# T_l_commande.net
KiCad netlist of a schematic drawn in Altium Designer
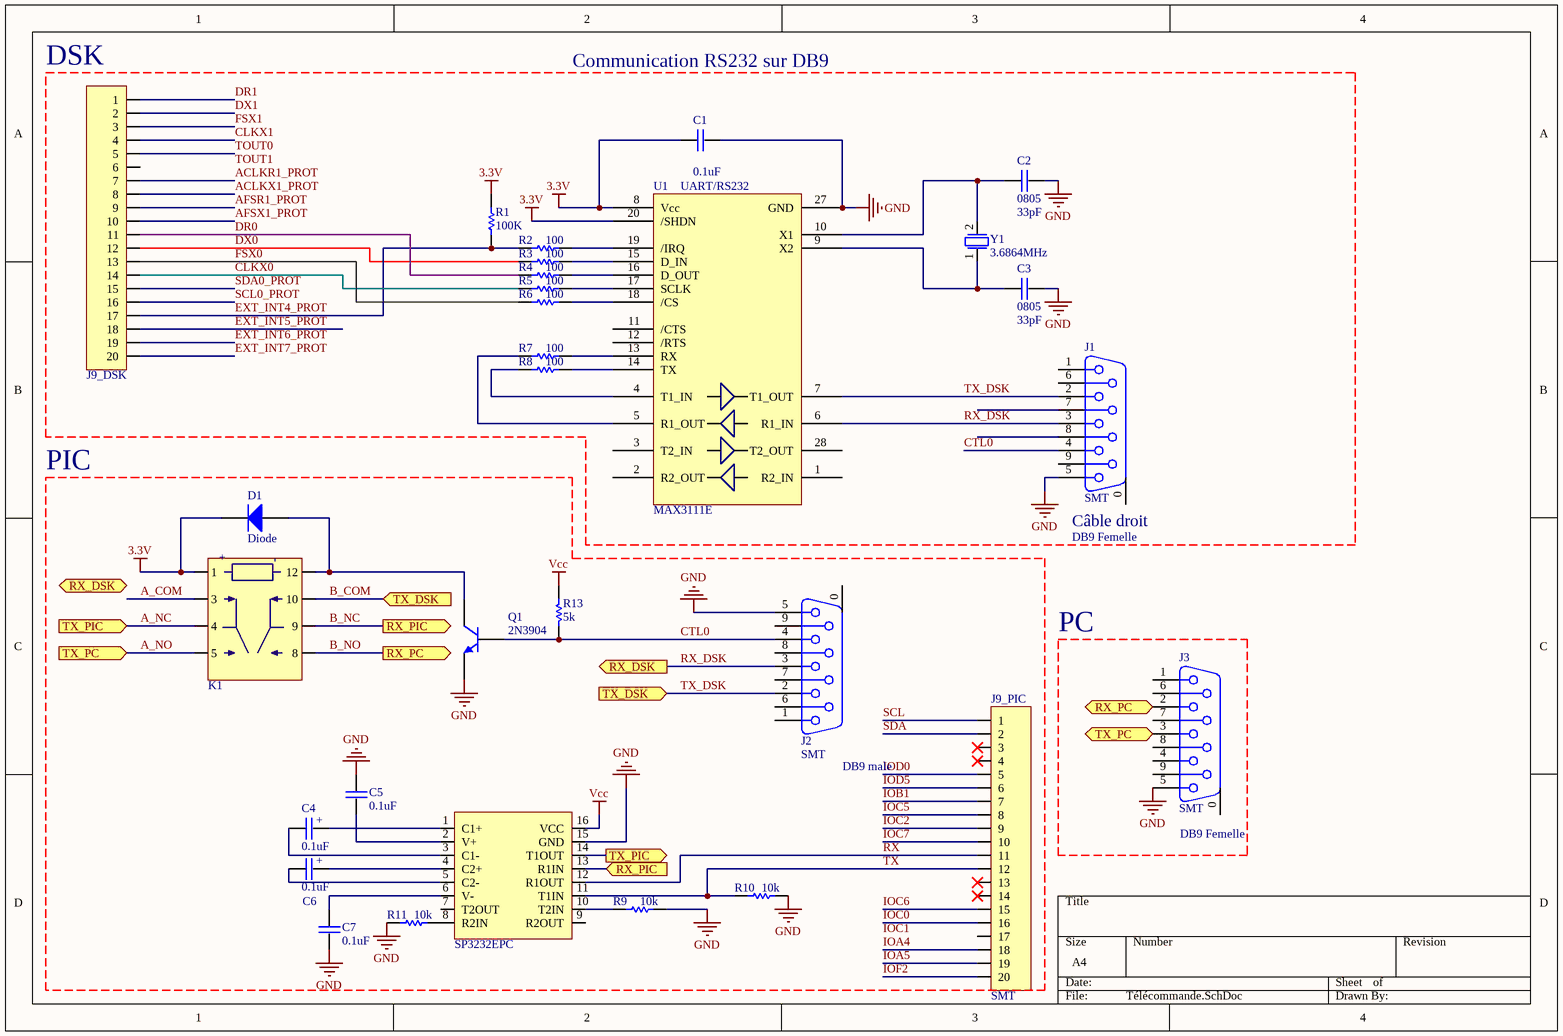
[diagram p0: Télécommande.SchDoc]

(export (version "E")
  (design (tool "Eeschema 10.0.6"))
  (components
    (comp (ref "C1")
      (value "0.1uF")
      (footprint "0805")
      (description "Condensateur céramique 0.1uF")
      (fields
        (field (name "MANUFACTURER") "Samsung Electro-Mechanics America, Inc.")
        (field (name "MFG PART NUMBER") "CL21B104KBCNNNC")
        (field (name "CREATEDBY") "Mathieu G-M")
        (field (name "VERIFIEDBY") "*")
      )
      (libsource (lib "SchLib_PCBs5") (part "Cap 0.1uF"))
    )
    (comp (ref "C2")
      (value "33pF")
      (footprint "0805")
      (description "Condensateur céramique 39pF")
      (fields
        (field (name "MANUFACTURER") "Samsung Electro-Mechanics America, Inc.")
        (field (name "MFG PART NUMBER") "CL21C390JBANNNC")
        (field (name "PACKAGE") "0805")
        (field (name "CREATEDBY") "Chloe Mireault-Lecourt")
        (field (name "VERIFIEDBY") "Olivier Bernard")
      )
      (libsource (lib "SchLib_PCBs5") (part "Cap 39pF"))
    )
    (comp (ref "C3")
      (value "33pF")
      (footprint "0805")
      (description "Condensateur céramique 39pF")
      (fields
        (field (name "MANUFACTURER") "Samsung Electro-Mechanics America, Inc.")
        (field (name "MFG PART NUMBER") "CL21C390JBANNNC")
        (field (name "PACKAGE") "0805")
        (field (name "CREATEDBY") "Chloe Mireault-Lecourt")
        (field (name "VERIFIEDBY") "Olivier Bernard")
      )
      (libsource (lib "SchLib_PCBs5") (part "Cap 39pF"))
    )
    (comp (ref "C4")
      (value "0.1uF")
      (footprint "0805")
      (description "Condensateur céramique 0.1uF")
      (fields
        (field (name "MANUFACTURER") "Samsung Electro-Mechanics America, Inc.")
        (field (name "MFG PART NUMBER") "CL21B104KBCNNNC")
        (field (name "CREATEDBY") "Mathieu G-M")
        (field (name "VERIFIEDBY") "*")
      )
      (libsource (lib "SchLib_PCBs5") (part "Cap 0.1uF"))
    )
    (comp (ref "C5")
      (value "0.1uF")
      (footprint "0805")
      (description "Condensateur céramique 0.1uF")
      (fields
        (field (name "MANUFACTURER") "Samsung Electro-Mechanics America, Inc.")
        (field (name "MFG PART NUMBER") "CL21B104KBCNNNC")
        (field (name "CREATEDBY") "Mathieu G-M")
        (field (name "VERIFIEDBY") "*")
      )
      (libsource (lib "SchLib_PCBs5") (part "Cap 0.1uF"))
    )
    (comp (ref "C6")
      (value "0.1uF")
      (footprint "0805")
      (description "Condensateur céramique 0.1uF")
      (fields
        (field (name "MANUFACTURER") "Samsung Electro-Mechanics America, Inc.")
        (field (name "MFG PART NUMBER") "CL21B104KBCNNNC")
        (field (name "CREATEDBY") "Mathieu G-M")
        (field (name "VERIFIEDBY") "*")
      )
      (libsource (lib "SchLib_PCBs5") (part "Cap 0.1uF"))
    )
    (comp (ref "C7")
      (value "0.1uF")
      (footprint "0805")
      (description "Condensateur céramique 0.1uF")
      (fields
        (field (name "MANUFACTURER") "Samsung Electro-Mechanics America, Inc.")
        (field (name "MFG PART NUMBER") "CL21B104KBCNNNC")
        (field (name "CREATEDBY") "Mathieu G-M")
        (field (name "VERIFIEDBY") "*")
      )
      (libsource (lib "SchLib_PCBs5") (part "Cap 0.1uF"))
    )
    (comp (ref "D1")
      (value "Diode")
      (footprint "SMC")
      (description "Default Diode")
      (fields (field (name "PUBLISHER") "Altium Limited"))
      (libsource (lib "Miscellaneous Devices") (part "Diode"))
    )
    (comp (ref "J1")
      (value "Conn DB9")
      (footprint "DB9 connector - SMT")
      (description "DB9 connecteur femelle")
      (fields
        (field (name "VOLTAGE") "300V")
        (field (name "MANUFACTURER") "Amphenol Commercial Products")
        (field (name "PACKAGE") "SMT")
        (field (name "CREATEDBY") "Mathieu G-M")
        (field (name "VERIFIEDBY") "*")
      )
      (libsource (lib "SchLib_PCBs5") (part "Conn DB9"))
    )
    (comp (ref "J2")
      (value "Conn DB9")
      (footprint "DB9 connector - SMT")
      (description "DB9 connecteur femelle")
      (fields
        (field (name "VOLTAGE") "300V")
        (field (name "MANUFACTURER") "Amphenol Commercial Products")
        (field (name "PACKAGE") "SMT")
        (field (name "CREATEDBY") "Mathieu G-M")
        (field (name "VERIFIEDBY") "*")
      )
      (libsource (lib "") (part "Conn DB9_1"))
    )
    (comp (ref "J3")
      (value "Conn DB9")
      (footprint "DB9 connector - SMT")
      (description "DB9 connecteur femelle")
      (fields
        (field (name "VOLTAGE") "300V")
        (field (name "MANUFACTURER") "Amphenol Commercial Products")
        (field (name "PACKAGE") "SMT")
        (field (name "CREATEDBY") "Mathieu G-M")
        (field (name "VERIFIEDBY") "*")
      )
      (libsource (lib "SchLib_PCBs5") (part "Conn DB9"))
    )
    (comp (ref "J9_DSK")
      (value "Conn20pinsF")
      (footprint "Conn_20_SMT")
      (description "Connecteur 20 pins F - pitch = 100mils")
      (fields
        (field (name "MANUFACTURER") "Sullins Connector Solutions")
        (field (name "MFG PART NUMBER") "NPTC102KFMS-RC")
        (field (name "CREATEDBY") "Olivier Bernard")
        (field (name "VERIFIEDBY") "*")
      )
      (libsource (lib "") (part "Conn20pinsF_1"))
    )
    (comp (ref "J9_PIC")
      (value "Conn20pinsF")
      (footprint "Conn_20_SMT")
      (description "Connecteur 20 pins F - pitch = 100mils")
      (fields
        (field (name "MANUFACTURER") "Sullins Connector Solutions")
        (field (name "MFG PART NUMBER") "NPTC102KFMS-RC")
        (field (name "PACKAGE") "SMT")
        (field (name "CREATEDBY") "Olivier Bernard")
        (field (name "VERIFIEDBY") "*")
      )
      (libsource (lib "SchLib_PCBs5") (part "Conn20pinsF"))
    )
    (comp (ref "K1")
      (value "Relay 3V")
      (footprint "Relay_3V")
      (fields
        (field (name "VOLTAGE") "Turn ON (2.4V), Turn OFF (0.3V)")
        (field (name "POWER") "coil Power (50mW)")
        (field (name "MANUFACTURER") "Panasonic Electric Works")
        (field (name "CREATEDBY") "Chloe Mireault-Lecourt")
        (field (name "VERIFIEDBY") "Olivier Bernard")
      )
      (libsource (lib "SchLib_PCBs5") (part "Relay 3V"))
    )
    (comp (ref "Q1")
      (value "2N3904")
      (footprint "TO-92A")
      (description "NPN General Purpose Amplifier")
      (fields (field (name "PUBLISHER") "Altium Limited"))
      (libsource (lib "Miscellaneous Devices") (part "2N3904"))
    )
    (comp (ref "R1")
      (value "100K")
      (footprint "0805")
      (description "Res 100k - SMT - 0805")
      (fields
        (field (name "POWER") "1/8W")
        (field (name "MANUFACTURER") "Yageo")
        (field (name "CREATEDBY") "Olivier Bernard")
        (field (name "VERIFIEDBY") "*")
      )
      (libsource (lib "SchLib_PCBs5") (part "Res100k_1%"))
    )
    (comp (ref "R2")
      (value "100")
      (footprint "0805")
      (description "Res 100- SMT - 0805")
      (fields
        (field (name "POWER") "1/8W")
        (field (name "MANUFACTURER") "Yageo")
        (field (name "CREATEDBY") "Olivier Bernard")
        (field (name "VERIFIEDBY") "*")
      )
      (libsource (lib "SchLib_PCBs5") (part "Res100_1%"))
    )
    (comp (ref "R3")
      (value "100")
      (footprint "0805")
      (description "Res 100- SMT - 0805")
      (fields
        (field (name "POWER") "1/8W")
        (field (name "MANUFACTURER") "Yageo")
        (field (name "CREATEDBY") "Olivier Bernard")
        (field (name "VERIFIEDBY") "*")
      )
      (libsource (lib "SchLib_PCBs5") (part "Res100_1%"))
    )
    (comp (ref "R4")
      (value "100")
      (footprint "0805")
      (description "Res 100- SMT - 0805")
      (fields
        (field (name "POWER") "1/8W")
        (field (name "MANUFACTURER") "Yageo")
        (field (name "CREATEDBY") "Olivier Bernard")
        (field (name "VERIFIEDBY") "*")
      )
      (libsource (lib "SchLib_PCBs5") (part "Res100_1%"))
    )
    (comp (ref "R5")
      (value "100")
      (footprint "0805")
      (description "Res 100- SMT - 0805")
      (fields
        (field (name "POWER") "1/8W")
        (field (name "MANUFACTURER") "Yageo")
        (field (name "CREATEDBY") "Olivier Bernard")
        (field (name "VERIFIEDBY") "*")
      )
      (libsource (lib "SchLib_PCBs5") (part "Res100_1%"))
    )
    (comp (ref "R6")
      (value "100")
      (footprint "0805")
      (description "Res 100- SMT - 0805")
      (fields
        (field (name "POWER") "1/8W")
        (field (name "MANUFACTURER") "Yageo")
        (field (name "CREATEDBY") "Olivier Bernard")
        (field (name "VERIFIEDBY") "*")
      )
      (libsource (lib "SchLib_PCBs5") (part "Res100_1%"))
    )
    (comp (ref "R7")
      (value "100")
      (footprint "0805")
      (description "Res 100- SMT - 0805")
      (fields
        (field (name "POWER") "1/8W")
        (field (name "MANUFACTURER") "Yageo")
        (field (name "CREATEDBY") "Olivier Bernard")
        (field (name "VERIFIEDBY") "*")
      )
      (libsource (lib "SchLib_PCBs5") (part "Res100_1%"))
    )
    (comp (ref "R8")
      (value "100")
      (footprint "0805")
      (description "Res 100- SMT - 0805")
      (fields
        (field (name "POWER") "1/8W")
        (field (name "MANUFACTURER") "Yageo")
        (field (name "CREATEDBY") "Olivier Bernard")
        (field (name "VERIFIEDBY") "*")
      )
      (libsource (lib "SchLib_PCBs5") (part "Res100_1%"))
    )
    (comp (ref "R9")
      (value "10k")
      (footprint "0805")
      (description "Res 100- SMT - 0805")
      (fields
        (field (name "POWER") "1/8W")
        (field (name "MANUFACTURER") "Yageo")
        (field (name "CREATEDBY") "Olivier Bernard")
        (field (name "VERIFIEDBY") "*")
      )
      (libsource (lib "SchLib_PCBs5") (part "Res100_1%"))
    )
    (comp (ref "R10")
      (value "10k")
      (footprint "0805")
      (description "Res 100- SMT - 0805")
      (fields
        (field (name "POWER") "1/8W")
        (field (name "MANUFACTURER") "Yageo")
        (field (name "CREATEDBY") "Olivier Bernard")
        (field (name "VERIFIEDBY") "*")
      )
      (libsource (lib "SchLib_PCBs5") (part "Res100_1%"))
    )
    (comp (ref "R11")
      (value "10k")
      (footprint "0805")
      (description "Res 100- SMT - 0805")
      (fields
        (field (name "POWER") "1/8W")
        (field (name "MANUFACTURER") "Yageo")
        (field (name "CREATEDBY") "Olivier Bernard")
        (field (name "VERIFIEDBY") "*")
      )
      (libsource (lib "SchLib_PCBs5") (part "Res100_1%"))
    )
    (comp (ref "R13")
      (value "5k")
      (footprint "0805")
      (description "Res 100k - SMT - 0805")
      (fields
        (field (name "POWER") "1/8W")
        (field (name "MANUFACTURER") "Yageo")
        (field (name "CREATEDBY") "Olivier Bernard")
        (field (name "VERIFIEDBY") "*")
      )
      (libsource (lib "SchLib_PCBs5") (part "Res100k_1%"))
    )
    (comp (ref "SP3232EPC")
      (value "SP3232EPC")
      (footprint "board-2-board40p_M")
      (description "40 Position Connector Header, Outer Shroud Contacts Surface Mount, Right Angle Gold")
      (fields
        (field (name "MANUFACTURER") "Hirose Electric Co Ltd")
        (field (name "MFG PART NUMBER") "FX18-40P-0.8SH")
        (field (name "HELPURL") "file:///C:/Users/Olivier/Downloads/FX18_05790002500_2d.pdf")
        (field (name "CREATEDBY") "BJong")
        (field (name "VERIFIEDBY") "Olivier Bernard")
      )
      (libsource (lib "SchLib_PCBs5") (part "SP3232EPC"))
    )
    (comp (ref "U1")
      (value "MAX3111E")
      (footprint "SOIC-28")
      (description "SPI/MICROWIRE Compatible UART and RS-232 Transceiver")
      (fields
        (field (name "MANUFACTURER") "Maxim Integrated")
        (field (name "MFG PART NUMBER") "MAX3111ECWI+G36")
        (field (name "CREATEDBY") "Chloe Mireault-Lecourt")
        (field (name "VERIFIEDBY") "Olivier Bernard")
      )
      (libsource (lib "SchLib_PCBs5") (part "MAX3111E"))
    )
    (comp (ref "Y1")
      (value "3.6864MHz")
      (footprint "Cristal HC49/US")
      (description "Crystal 3.6864MHz - SMT - HC49/US")
      (fields
        (field (name "MANUFACTURER") "Fox Electronics")
        (field (name "MFG PART NUMBER") "FOXSDLF/0368-20")
        (field (name "CREATEDBY") "Chloe Mireault-Lecourt")
        (field (name "VERIFIEDBY") "Olivier Bernard")
      )
      (libsource (lib "SchLib_PCBs5") (part "Crystal_3.6864"))
    )
  )
  (nets
    (net (code "1") (name "/ACLKR1_PROT") (class "Default")
      (node (ref "J9_DSK") (pin "7") (pinfunction "7_7") (pintype "passive"))
    )
    (net (code "2") (name "/ACLKX1_PROT") (class "Default")
      (node (ref "J9_DSK") (pin "8") (pinfunction "8_8") (pintype "passive"))
    )
    (net (code "3") (name "/AFSR1_PROT") (class "Default")
      (node (ref "J9_DSK") (pin "9") (pinfunction "9_9") (pintype "passive"))
    )
    (net (code "4") (name "/AFSX1_PROT") (class "Default")
      (node (ref "J9_DSK") (pin "10") (pinfunction "10_10") (pintype "passive"))
    )
    (net (code "5") (name "/A_COM") (class "Default")
      (node (ref "K1") (pin "3") (pinfunction "3_3") (pintype "passive"))
    )
    (net (code "6") (name "/A_NC") (class "Default")
      (node (ref "K1") (pin "4") (pinfunction "4_4") (pintype "passive"))
      (node (ref "SP3232EPC") (pin "14") (pinfunction "T1OUT_14") (pintype "passive"))
    )
    (net (code "7") (name "/A_NO") (class "Default")
      (node (ref "J3") (pin "3") (pinfunction "3_3") (pintype "passive"))
      (node (ref "K1") (pin "5") (pinfunction "5_5") (pintype "passive"))
    )
    (net (code "8") (name "/B_COM") (class "Default")
      (node (ref "J1") (pin "2") (pinfunction "2_2") (pintype "passive"))
      (node (ref "J2") (pin "2") (pinfunction "2_2") (pintype "passive"))
      (node (ref "K1") (pin "10") (pinfunction "10_10") (pintype "passive"))
      (node (ref "U1") (pin "7") (pinfunction "T1_OUT_7") (pintype "passive"))
    )
    (net (code "9") (name "/B_NC") (class "Default")
      (node (ref "K1") (pin "9") (pinfunction "9_9") (pintype "passive"))
      (node (ref "SP3232EPC") (pin "13") (pinfunction "R1IN_13") (pintype "passive"))
    )
    (net (code "10") (name "/B_NO") (class "Default")
      (node (ref "J3") (pin "2") (pinfunction "2_2") (pintype "passive"))
      (node (ref "K1") (pin "8") (pinfunction "8_8") (pintype "passive"))
    )
    (net (code "11") (name "/CLKX0") (class "Default")
      (node (ref "J9_DSK") (pin "14") (pinfunction "14_14") (pintype "passive"))
      (node (ref "R5") (pin "1") (pinfunction "1_1") (pintype "passive"))
    )
    (net (code "12") (name "/CLKX1") (class "Default")
      (node (ref "J9_DSK") (pin "4") (pinfunction "4_4") (pintype "passive"))
    )
    (net (code "13") (name "/CTL0") (class "Default")
      (node (ref "J1") (pin "4") (pinfunction "4_4") (pintype "passive"))
      (node (ref "J2") (pin "4") (pinfunction "4_4") (pintype "passive"))
      (node (ref "Q1") (pin "2") (pinfunction "B_2") (pintype "passive"))
      (node (ref "R13") (pin "1") (pinfunction "1_1") (pintype "passive"))
    )
    (net (code "14") (name "/DR0") (class "Default")
      (node (ref "J9_DSK") (pin "11") (pinfunction "11_11") (pintype "passive"))
      (node (ref "R4") (pin "1") (pinfunction "1_1") (pintype "passive"))
    )
    (net (code "15") (name "/DR1") (class "Default")
      (node (ref "J9_DSK") (pin "1") (pinfunction "1_1") (pintype "passive"))
    )
    (net (code "16") (name "/DX0") (class "Default")
      (node (ref "J9_DSK") (pin "12") (pinfunction "12_12") (pintype "passive"))
      (node (ref "R3") (pin "1") (pinfunction "1_1") (pintype "passive"))
    )
    (net (code "17") (name "/DX1") (class "Default")
      (node (ref "J9_DSK") (pin "2") (pinfunction "2_2") (pintype "passive"))
    )
    (net (code "18") (name "/EXT_INT4_PROT") (class "Default")
      (node (ref "J9_DSK") (pin "17") (pinfunction "17_17") (pintype "passive"))
      (node (ref "R1") (pin "1") (pinfunction "1_1") (pintype "passive"))
      (node (ref "R2") (pin "1") (pinfunction "1_1") (pintype "passive"))
    )
    (net (code "19") (name "/EXT_INT5_PROT") (class "Default")
      (node (ref "J9_DSK") (pin "18") (pinfunction "18_18") (pintype "passive"))
    )
    (net (code "20") (name "/EXT_INT6_PROT") (class "Default")
      (node (ref "J9_DSK") (pin "19") (pinfunction "19_19") (pintype "passive"))
    )
    (net (code "21") (name "/EXT_INT7_PROT") (class "Default")
      (node (ref "J9_DSK") (pin "20") (pinfunction "20_20") (pintype "passive"))
    )
    (net (code "22") (name "/FSX0") (class "Default")
      (node (ref "J9_DSK") (pin "13") (pinfunction "13_13") (pintype "passive"))
      (node (ref "R6") (pin "1") (pinfunction "1_1") (pintype "passive"))
    )
    (net (code "23") (name "/FSX1") (class "Default")
      (node (ref "J9_DSK") (pin "3") (pinfunction "3_3") (pintype "passive"))
    )
    (net (code "24") (name "/IOA4") (class "Default")
      (node (ref "J9_PIC") (pin "18") (pinfunction "18_18") (pintype "passive"))
    )
    (net (code "25") (name "/IOA5") (class "Default")
      (node (ref "J9_PIC") (pin "19") (pinfunction "19_19") (pintype "passive"))
    )
    (net (code "26") (name "/IOB1") (class "Default")
      (node (ref "J9_PIC") (pin "7") (pinfunction "7_7") (pintype "passive"))
    )
    (net (code "27") (name "/IOC0") (class "Default")
      (node (ref "J9_PIC") (pin "16") (pinfunction "16_16") (pintype "passive"))
    )
    (net (code "29") (name "/IOC2") (class "Default")
      (node (ref "J9_PIC") (pin "9") (pinfunction "9_9") (pintype "passive"))
    )
    (net (code "30") (name "/IOC5") (class "Default")
      (node (ref "J9_PIC") (pin "8") (pinfunction "8_8") (pintype "passive"))
    )
    (net (code "31") (name "/IOC6") (class "Default")
      (node (ref "J9_PIC") (pin "15") (pinfunction "15_15") (pintype "passive"))
    )
    (net (code "32") (name "/IOC7") (class "Default")
      (node (ref "J9_PIC") (pin "10") (pinfunction "10_10") (pintype "passive"))
    )
    (net (code "33") (name "/IOD0") (class "Default")
      (node (ref "J9_PIC") (pin "5") (pinfunction "5_5") (pintype "passive"))
    )
    (net (code "34") (name "/IOD5") (class "Default")
      (node (ref "J9_PIC") (pin "6") (pinfunction "6_6") (pintype "passive"))
    )
    (net (code "35") (name "/IOF2") (class "Default")
      (node (ref "J9_PIC") (pin "20") (pinfunction "20_20") (pintype "passive"))
    )
    (net (code "36") (name "/RX") (class "Default")
      (node (ref "J9_PIC") (pin "11") (pinfunction "11_11") (pintype "passive"))
      (node (ref "SP3232EPC") (pin "12") (pinfunction "R1OUT_12") (pintype "passive"))
    )
    (net (code "37") (name "/RX_DSK") (class "Default")
      (node (ref "J1") (pin "3") (pinfunction "3_3") (pintype "passive"))
      (node (ref "J2") (pin "3") (pinfunction "3_3") (pintype "passive"))
      (node (ref "U1") (pin "6") (pinfunction "R1_IN_6") (pintype "passive"))
    )
    (net (code "38") (name "/SCL") (class "Default")
      (node (ref "J9_PIC") (pin "1") (pinfunction "1_1") (pintype "passive"))
    )
    (net (code "39") (name "/SCL0_PROT") (class "Default")
      (node (ref "J9_DSK") (pin "16") (pinfunction "16_16") (pintype "passive"))
    )
    (net (code "40") (name "/SDA") (class "Default")
      (node (ref "J9_PIC") (pin "2") (pinfunction "2_2") (pintype "passive"))
    )
    (net (code "41") (name "/SDA0_PROT") (class "Default")
      (node (ref "J9_DSK") (pin "15") (pinfunction "15_15") (pintype "passive"))
    )
    (net (code "42") (name "/TOUT0") (class "Default")
      (node (ref "J9_DSK") (pin "5") (pinfunction "5_5") (pintype "passive"))
    )
    (net (code "44") (name "/TX") (class "Default")
      (node (ref "J9_PIC") (pin "12") (pinfunction "12_12") (pintype "passive"))
      (node (ref "R10") (pin "1") (pinfunction "1_1") (pintype "passive"))
      (node (ref "SP3232EPC") (pin "11") (pinfunction "T1IN_11") (pintype "passive"))
    )
    (net (code "45") (name "3.3V") (class "Default")
      (node (ref "C1") (pin "2") (pinfunction "2_2") (pintype "passive"))
      (node (ref "D1") (pin "2") (pinfunction "K_2") (pintype "passive"))
      (node (ref "K1") (pin "1") (pinfunction "1_1") (pintype "passive"))
      (node (ref "R1") (pin "2") (pinfunction "2_2") (pintype "passive"))
      (node (ref "U1") (pin "20") (pinfunction "/SHDN_20") (pintype "passive"))
      (node (ref "U1") (pin "8") (pinfunction "Vcc_8") (pintype "passive"))
    )
    (net (code "46") (name "GND") (class "Default")
      (node (ref "C1") (pin "1") (pinfunction "1_1") (pintype "passive"))
      (node (ref "C2") (pin "2") (pinfunction "2_2") (pintype "passive"))
      (node (ref "C3") (pin "2") (pinfunction "2_2") (pintype "passive"))
      (node (ref "C5") (pin "2") (pinfunction "2_2") (pintype "passive"))
      (node (ref "C7") (pin "2") (pinfunction "2_2") (pintype "passive"))
      (node (ref "J1") (pin "5") (pinfunction "5_5") (pintype "passive"))
      (node (ref "J2") (pin "5") (pinfunction "5_5") (pintype "passive"))
      (node (ref "J3") (pin "5") (pinfunction "5_5") (pintype "passive"))
      (node (ref "Q1") (pin "1") (pinfunction "E_1") (pintype "passive"))
      (node (ref "R10") (pin "2") (pinfunction "2_2") (pintype "passive"))
      (node (ref "R11") (pin "1") (pinfunction "1_1") (pintype "passive"))
      (node (ref "R9") (pin "2") (pinfunction "2_2") (pintype "passive"))
      (node (ref "SP3232EPC") (pin "15") (pinfunction "GND_15") (pintype "passive"))
      (node (ref "U1") (pin "27") (pinfunction "GND_27") (pintype "passive"))
    )
    (net (code "47") (name "Net-(D1-A)") (class "Default")
      (node (ref "D1") (pin "1") (pinfunction "A_1") (pintype "passive"))
      (node (ref "K1") (pin "12") (pinfunction "12_12") (pintype "passive"))
      (node (ref "Q1") (pin "3") (pinfunction "C_3") (pintype "passive"))
    )
    (net (code "48") (name "Net-(SP3232EPC-C1+)") (class "Default")
      (node (ref "C4") (pin "2") (pinfunction "2_2") (pintype "passive"))
      (node (ref "SP3232EPC") (pin "1") (pinfunction "C1+_1") (pintype "passive"))
    )
    (net (code "49") (name "Net-(SP3232EPC-C1-)") (class "Default")
      (node (ref "C4") (pin "1") (pinfunction "1_1") (pintype "passive"))
      (node (ref "SP3232EPC") (pin "3") (pinfunction "C1-_3") (pintype "passive"))
    )
    (net (code "50") (name "Net-(SP3232EPC-C2+)") (class "Default")
      (node (ref "C6") (pin "2") (pinfunction "2_2") (pintype "passive"))
      (node (ref "SP3232EPC") (pin "4") (pinfunction "C2+_4") (pintype "passive"))
    )
    (net (code "51") (name "Net-(SP3232EPC-C2-)") (class "Default")
      (node (ref "C6") (pin "1") (pinfunction "1_1") (pintype "passive"))
      (node (ref "SP3232EPC") (pin "5") (pinfunction "C2-_5") (pintype "passive"))
    )
    (net (code "52") (name "Net-(SP3232EPC-R2IN)") (class "Default")
      (node (ref "R11") (pin "2") (pinfunction "2_2") (pintype "passive"))
      (node (ref "SP3232EPC") (pin "8") (pinfunction "R2IN_8") (pintype "passive"))
    )
    (net (code "53") (name "Net-(SP3232EPC-T2IN)") (class "Default")
      (node (ref "R9") (pin "1") (pinfunction "1_1") (pintype "passive"))
      (node (ref "SP3232EPC") (pin "10") (pinfunction "T2IN_10") (pintype "passive"))
    )
    (net (code "54") (name "Net-(SP3232EPC-V+)") (class "Default")
      (node (ref "C5") (pin "1") (pinfunction "1_1") (pintype "passive"))
      (node (ref "SP3232EPC") (pin "2") (pinfunction "V+_2") (pintype "passive"))
    )
    (net (code "55") (name "Net-(SP3232EPC-V-)") (class "Default")
      (node (ref "C7") (pin "1") (pinfunction "1_1") (pintype "passive"))
      (node (ref "SP3232EPC") (pin "6") (pinfunction "V-_6") (pintype "passive"))
    )
    (net (code "56") (name "Net-(U1-D_IN)") (class "Default")
      (node (ref "R3") (pin "2") (pinfunction "2_2") (pintype "passive"))
      (node (ref "U1") (pin "15") (pinfunction "D_IN_15") (pintype "passive"))
    )
    (net (code "57") (name "Net-(U1-D_OUT)") (class "Default")
      (node (ref "R4") (pin "2") (pinfunction "2_2") (pintype "passive"))
      (node (ref "U1") (pin "16") (pinfunction "D_OUT_16") (pintype "passive"))
    )
    (net (code "58") (name "Net-(U1-R1_OUT)") (class "Default")
      (node (ref "R7") (pin "1") (pinfunction "1_1") (pintype "passive"))
      (node (ref "U1") (pin "5") (pinfunction "R1_OUT_5") (pintype "passive"))
    )
    (net (code "59") (name "Net-(U1-RX)") (class "Default")
      (node (ref "R7") (pin "2") (pinfunction "2_2") (pintype "passive"))
      (node (ref "U1") (pin "13") (pinfunction "RX_13") (pintype "passive"))
    )
    (net (code "60") (name "Net-(U1-SCLK)") (class "Default")
      (node (ref "R5") (pin "2") (pinfunction "2_2") (pintype "passive"))
      (node (ref "U1") (pin "17") (pinfunction "SCLK_17") (pintype "passive"))
    )
    (net (code "61") (name "Net-(U1-T1_IN)") (class "Default")
      (node (ref "R8") (pin "1") (pinfunction "1_1") (pintype "passive"))
      (node (ref "U1") (pin "4") (pinfunction "T1_IN_4") (pintype "passive"))
    )
    (net (code "62") (name "Net-(U1-TX)") (class "Default")
      (node (ref "R8") (pin "2") (pinfunction "2_2") (pintype "passive"))
      (node (ref "U1") (pin "14") (pinfunction "TX_14") (pintype "passive"))
    )
    (net (code "63") (name "Net-(U1-X1)") (class "Default")
      (node (ref "C2") (pin "1") (pinfunction "1_1") (pintype "passive"))
      (node (ref "U1") (pin "10") (pinfunction "X1_10") (pintype "passive"))
      (node (ref "Y1") (pin "2") (pinfunction "2_2") (pintype "passive"))
    )
    (net (code "64") (name "Net-(U1-X2)") (class "Default")
      (node (ref "C3") (pin "1") (pinfunction "1_1") (pintype "passive"))
      (node (ref "U1") (pin "9") (pinfunction "X2_9") (pintype "passive"))
      (node (ref "Y1") (pin "1") (pinfunction "1_1") (pintype "passive"))
    )
    (net (code "65") (name "Net-(U1-{slash}CS)") (class "Default")
      (node (ref "R6") (pin "2") (pinfunction "2_2") (pintype "passive"))
      (node (ref "U1") (pin "18") (pinfunction "/CS_18") (pintype "passive"))
    )
    (net (code "66") (name "Net-(U1-{slash}IRQ)") (class "Default")
      (node (ref "R2") (pin "2") (pinfunction "2_2") (pintype "passive"))
      (node (ref "U1") (pin "19") (pinfunction "/IRQ_19") (pintype "passive"))
    )
    (net (code "67") (name "Vcc") (class "Default")
      (node (ref "R13") (pin "2") (pinfunction "2_2") (pintype "passive"))
      (node (ref "SP3232EPC") (pin "16") (pinfunction "VCC_16") (pintype "passive"))
    )
    (net (code "68") (name "unconnected-(J1-Pad0)") (class "Default")
      (node (ref "J1") (pin "0") (pinfunction "0_0") (pintype "passive"))
    )
    (net (code "69") (name "unconnected-(J1-Pad1)") (class "Default")
      (node (ref "J1") (pin "1") (pinfunction "1_1") (pintype "passive"))
    )
    (net (code "70") (name "unconnected-(J1-Pad6)") (class "Default")
      (node (ref "J1") (pin "6") (pinfunction "6_6") (pintype "passive"))
    )
    (net (code "71") (name "unconnected-(J1-Pad7)") (class "Default")
      (node (ref "J1") (pin "7") (pinfunction "7_7") (pintype "passive"))
    )
    (net (code "72") (name "unconnected-(J1-Pad8)") (class "Default")
      (node (ref "J1") (pin "8") (pinfunction "8_8") (pintype "passive"))
    )
    (net (code "73") (name "unconnected-(J1-Pad9)") (class "Default")
      (node (ref "J1") (pin "9") (pinfunction "9_9") (pintype "passive"))
    )
    (net (code "74") (name "unconnected-(J2-Pad0)") (class "Default")
      (node (ref "J2") (pin "0") (pinfunction "0_0") (pintype "passive"))
    )
    (net (code "75") (name "unconnected-(J2-Pad1)") (class "Default")
      (node (ref "J2") (pin "1") (pinfunction "1_1") (pintype "passive"))
    )
    (net (code "76") (name "unconnected-(J2-Pad6)") (class "Default")
      (node (ref "J2") (pin "6") (pinfunction "6_6") (pintype "passive"))
    )
    (net (code "77") (name "unconnected-(J2-Pad7)") (class "Default")
      (node (ref "J2") (pin "7") (pinfunction "7_7") (pintype "passive"))
    )
    (net (code "78") (name "unconnected-(J2-Pad8)") (class "Default")
      (node (ref "J2") (pin "8") (pinfunction "8_8") (pintype "passive"))
    )
    (net (code "79") (name "unconnected-(J2-Pad9)") (class "Default")
      (node (ref "J2") (pin "9") (pinfunction "9_9") (pintype "passive"))
    )
    (net (code "80") (name "unconnected-(J3-Pad0)") (class "Default")
      (node (ref "J3") (pin "0") (pinfunction "0_0") (pintype "passive"))
    )
    (net (code "81") (name "unconnected-(J3-Pad1)") (class "Default")
      (node (ref "J3") (pin "1") (pinfunction "1_1") (pintype "passive"))
    )
    (net (code "82") (name "unconnected-(J3-Pad4)") (class "Default")
      (node (ref "J3") (pin "4") (pinfunction "4_4") (pintype "passive"))
    )
    (net (code "83") (name "unconnected-(J3-Pad6)") (class "Default")
      (node (ref "J3") (pin "6") (pinfunction "6_6") (pintype "passive"))
    )
    (net (code "84") (name "unconnected-(J3-Pad7)") (class "Default")
      (node (ref "J3") (pin "7") (pinfunction "7_7") (pintype "passive"))
    )
    (net (code "85") (name "unconnected-(J3-Pad8)") (class "Default")
      (node (ref "J3") (pin "8") (pinfunction "8_8") (pintype "passive"))
    )
    (net (code "86") (name "unconnected-(J3-Pad9)") (class "Default")
      (node (ref "J3") (pin "9") (pinfunction "9_9") (pintype "passive"))
    )
    (net (code "87") (name "unconnected-(J9_DSK-Pad6)") (class "Default")
      (node (ref "J9_DSK") (pin "6") (pinfunction "6_6") (pintype "passive"))
    )
    (net (code "88") (name "unconnected-(J9_PIC-Pad3)") (class "Default")
      (node (ref "J9_PIC") (pin "3") (pinfunction "3_3") (pintype "passive+no_connect"))
    )
    (net (code "89") (name "unconnected-(J9_PIC-Pad4)") (class "Default")
      (node (ref "J9_PIC") (pin "4") (pinfunction "4_4") (pintype "passive+no_connect"))
    )
    (net (code "90") (name "unconnected-(J9_PIC-Pad13)") (class "Default")
      (node (ref "J9_PIC") (pin "13") (pinfunction "13_13") (pintype "passive+no_connect"))
    )
    (net (code "91") (name "unconnected-(J9_PIC-Pad14)") (class "Default")
      (node (ref "J9_PIC") (pin "14") (pinfunction "14_14") (pintype "passive+no_connect"))
    )
    (net (code "92") (name "unconnected-(J9_PIC-Pad17)") (class "Default")
      (node (ref "J9_PIC") (pin "17") (pinfunction "17_17") (pintype "passive"))
    )
    (net (code "93") (name "unconnected-(SP3232EPC-R2OUT-Pad9)") (class "Default")
      (node (ref "SP3232EPC") (pin "9") (pinfunction "R2OUT_9") (pintype "passive"))
    )
    (net (code "94") (name "unconnected-(SP3232EPC-T2OUT-Pad7)") (class "Default")
      (node (ref "SP3232EPC") (pin "7") (pinfunction "T2OUT_7") (pintype "passive"))
    )
    (net (code "95") (name "unconnected-(U1-C1+-Pad22)") (class "Default")
      (node (ref "U1") (pin "22") (pinfunction "C1+_22") (pintype "passive"))
    )
    (net (code "96") (name "unconnected-(U1-C1--Pad23)") (class "Default")
      (node (ref "U1") (pin "23") (pinfunction "C1-_23") (pintype "passive"))
    )
    (net (code "97") (name "unconnected-(U1-C2+-Pad24)") (class "Default")
      (node (ref "U1") (pin "24") (pinfunction "C2+_24") (pintype "passive"))
    )
    (net (code "98") (name "unconnected-(U1-C2--Pad25)") (class "Default")
      (node (ref "U1") (pin "25") (pinfunction "C2-_25") (pintype "passive"))
    )
    (net (code "99") (name "unconnected-(U1-R2_IN-Pad1)") (class "Default")
      (node (ref "U1") (pin "1") (pinfunction "R2_IN_1") (pintype "passive"))
    )
    (net (code "100") (name "unconnected-(U1-R2_OUT-Pad2)") (class "Default")
      (node (ref "U1") (pin "2") (pinfunction "R2_OUT_2") (pintype "passive"))
    )
    (net (code "101") (name "unconnected-(U1-T2_IN-Pad3)") (class "Default")
      (node (ref "U1") (pin "3") (pinfunction "T2_IN_3") (pintype "passive"))
    )
    (net (code "102") (name "unconnected-(U1-T2_OUT-Pad28)") (class "Default")
      (node (ref "U1") (pin "28") (pinfunction "T2_OUT_28") (pintype "passive"))
    )
    (net (code "103") (name "unconnected-(U1-V+-Pad21)") (class "Default")
      (node (ref "U1") (pin "21") (pinfunction "V+_21") (pintype "passive"))
    )
    (net (code "104") (name "unconnected-(U1-V--Pad26)") (class "Default")
      (node (ref "U1") (pin "26") (pinfunction "V-_26") (pintype "passive"))
    )
    (net (code "105") (name "unconnected-(U1-{slash}CTS-Pad11)") (class "Default")
      (node (ref "U1") (pin "11") (pinfunction "/CTS_11") (pintype "passive"))
    )
    (net (code "106") (name "unconnected-(U1-{slash}RTS-Pad12)") (class "Default")
      (node (ref "U1") (pin "12") (pinfunction "/RTS_12") (pintype "passive"))
    )
  )
)
